# 2020-02-LPD3806-orig.net
KiCad netlist of a schematic drawn in EAGLE
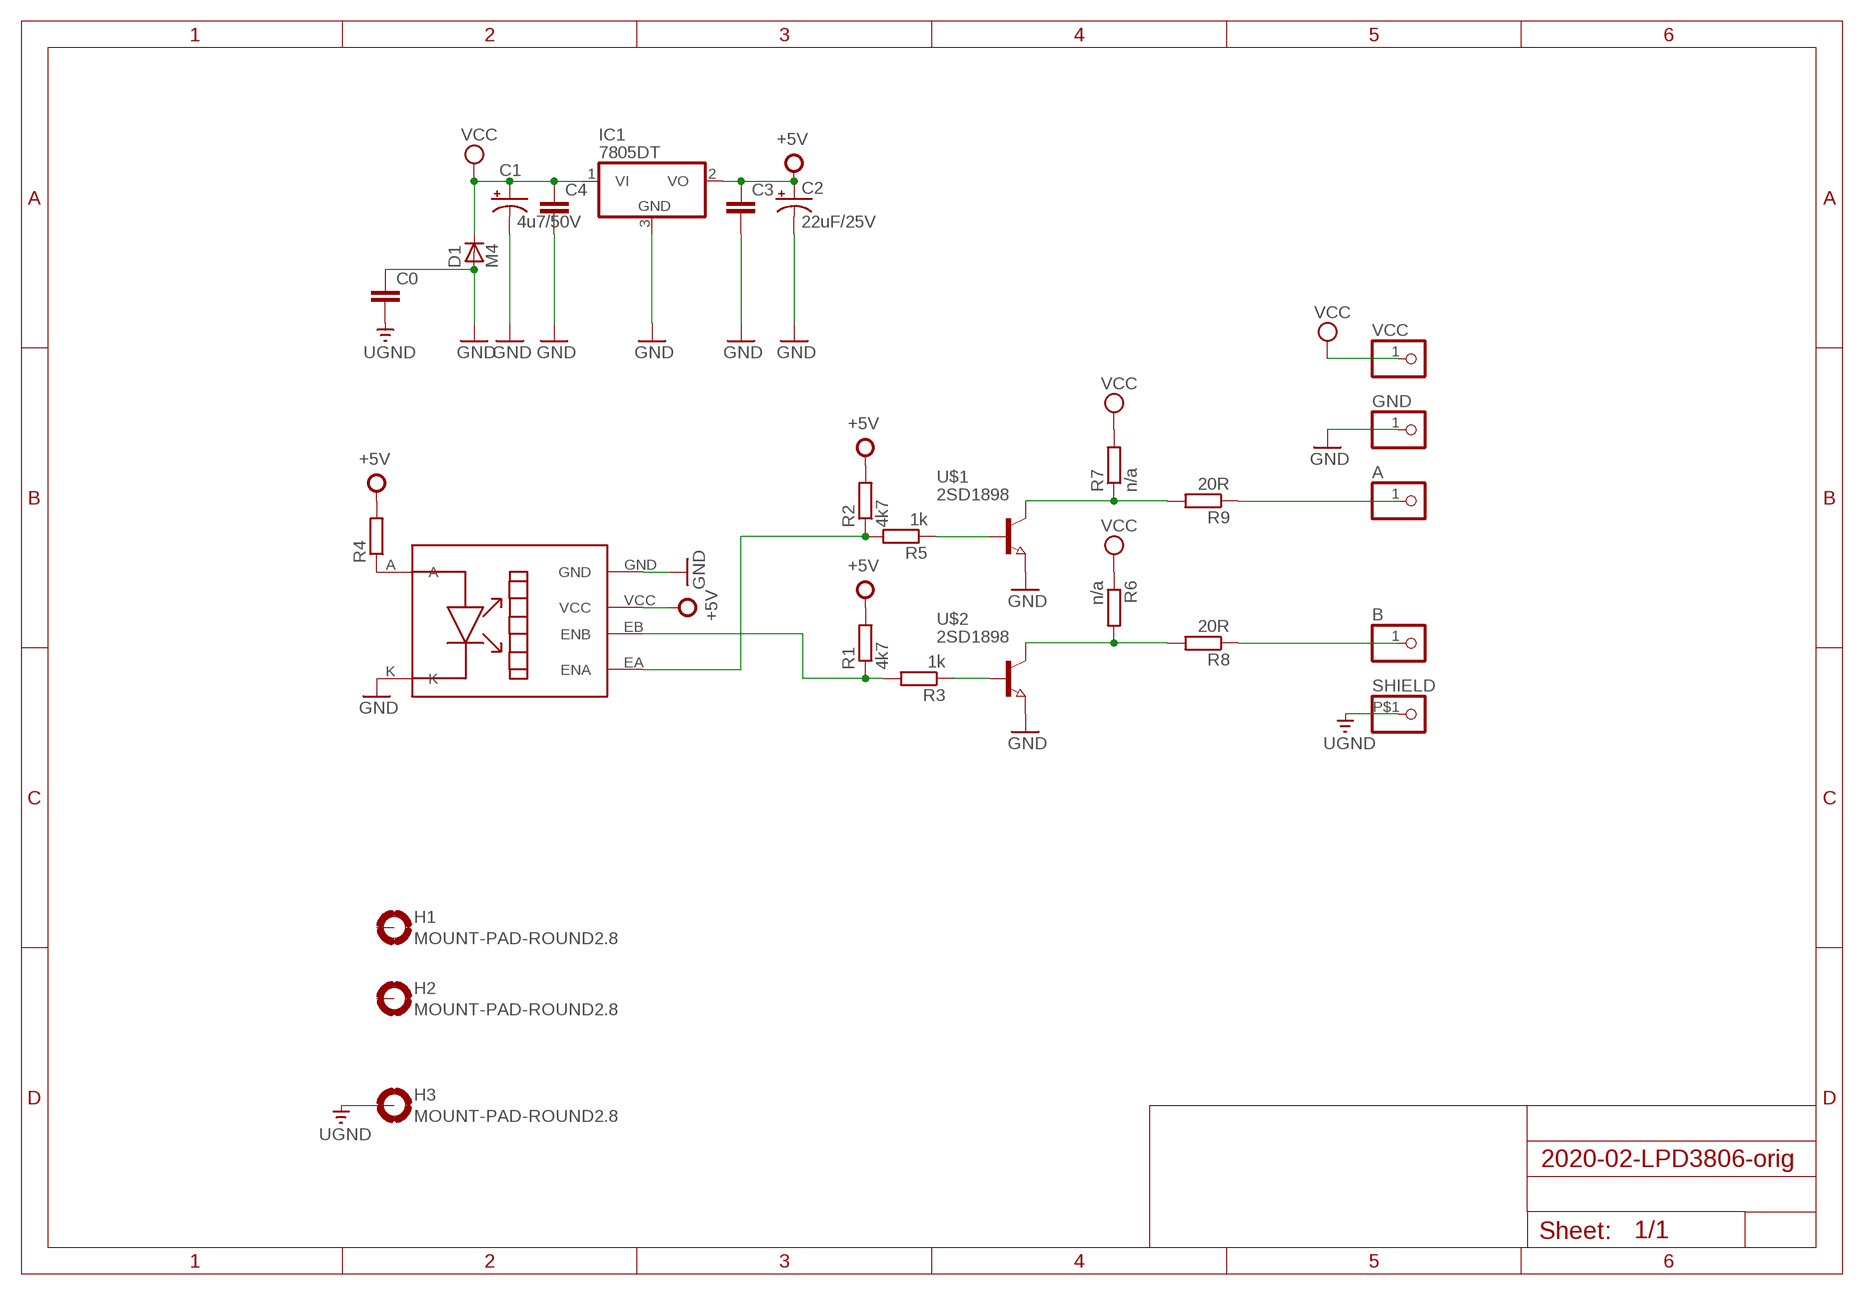
[diagram p0: schematic, sheet 1]

(export (version "E")
  (design (tool "Eeschema 10.0.6"))
  (components
    (comp (ref "A")
      (value "PINHD-1X1")
      (footprint "eagle-import:1X01")
      (libsource (lib "eagle-import") (part "PINHD-1X1"))
    )
    (comp (ref "B")
      (value "PINHD-1X1")
      (footprint "eagle-import:1X01")
      (libsource (lib "eagle-import") (part "PINHD-1X1"))
    )
    (comp (ref "C0")
      (value "C-EUC1206")
      (footprint "eagle-import:C1206")
      (libsource (lib "eagle-import") (part "C-EUC1206"))
    )
    (comp (ref "C1")
      (value "4u7/50V")
      (footprint "eagle-import:153CLV-0405")
      (libsource (lib "eagle-import") (part "CPOL-US153CLV-0405"))
    )
    (comp (ref "C2")
      (value "22uF/25V")
      (footprint "eagle-import:153CLV-0505")
      (libsource (lib "eagle-import") (part "CPOL-US153CLV-0505"))
    )
    (comp (ref "C3")
      (value "C-EUC0805")
      (footprint "eagle-import:C0805")
      (libsource (lib "eagle-import") (part "C-EUC0805"))
    )
    (comp (ref "C4")
      (value "C-EUC0805")
      (footprint "eagle-import:C0805")
      (libsource (lib "eagle-import") (part "C-EUC0805"))
    )
    (comp (ref "D1")
      (value "M4")
      (footprint "eagle-import:SOD-123")
      (libsource (lib "eagle-import") (part "DIODESOD-123"))
    )
    (comp (ref "GND")
      (value "PINHD-1X1")
      (footprint "eagle-import:1X01")
      (libsource (lib "eagle-import") (part "PINHD-1X1"))
    )
    (comp (ref "H1")
      (value "MOUNT-PAD-ROUND2.8")
      (footprint "eagle-import:2,8-PAD")
      (libsource (lib "eagle-import") (part "MOUNT-PAD-ROUND2.8"))
    )
    (comp (ref "H2")
      (value "MOUNT-PAD-ROUND2.8")
      (footprint "eagle-import:2,8-PAD")
      (libsource (lib "eagle-import") (part "MOUNT-PAD-ROUND2.8"))
    )
    (comp (ref "H3")
      (value "MOUNT-PAD-ROUND2.8")
      (footprint "eagle-import:2,8-PAD")
      (libsource (lib "eagle-import") (part "MOUNT-PAD-ROUND2.8"))
    )
    (comp (ref "IC1")
      (value "7805DT")
      (footprint "eagle-import:TO252")
      (libsource (lib "eagle-import") (part "78DT05"))
    )
    (comp (ref "R1")
      (value "4k7")
      (footprint "eagle-import:R0805")
      (libsource (lib "eagle-import") (part "R-EU_R0805"))
    )
    (comp (ref "R2")
      (value "4k7")
      (footprint "eagle-import:R0805")
      (libsource (lib "eagle-import") (part "R-EU_R0805"))
    )
    (comp (ref "R3")
      (value "1k")
      (footprint "eagle-import:R0805")
      (libsource (lib "eagle-import") (part "R-EU_R0805"))
    )
    (comp (ref "R4")
      (value "R-EU_R1206")
      (footprint "eagle-import:R1206")
      (libsource (lib "eagle-import") (part "R-EU_R1206"))
    )
    (comp (ref "R5")
      (value "1k")
      (footprint "eagle-import:R0805")
      (libsource (lib "eagle-import") (part "R-EU_R0805"))
    )
    (comp (ref "R6")
      (value "n/a")
      (footprint "eagle-import:R1206")
      (libsource (lib "eagle-import") (part "R-EU_R1206"))
    )
    (comp (ref "R7")
      (value "n/a")
      (footprint "eagle-import:R1206")
      (libsource (lib "eagle-import") (part "R-EU_R1206"))
    )
    (comp (ref "R8")
      (value "20R")
      (footprint "eagle-import:R1206")
      (libsource (lib "eagle-import") (part "R-EU_R1206"))
    )
    (comp (ref "R9")
      (value "20R")
      (footprint "eagle-import:R1206")
      (libsource (lib "eagle-import") (part "R-EU_R1206"))
    )
    (comp (ref "SHIELD")
      (value "PINHD-1X1-BIGPOGO")
      (footprint "eagle-import:1X1-BIGPOGO")
      (libsource (lib "eagle-import") (part "PINHD-1X1-BIGPOGO"))
    )
    (comp (ref "U$1")
      (value "2SD1898")
      (footprint "eagle-import:SOT-89")
      (libsource (lib "eagle-import") (part "2SD1898"))
    )
    (comp (ref "U$2")
      (value "2SD1898")
      (footprint "eagle-import:SOT-89")
      (libsource (lib "eagle-import") (part "2SD1898"))
    )
    (comp (ref "U$3")
      (value "N30-6841")
      (footprint "eagle-import:N30-6841")
      (libsource (lib "eagle-import") (part "N30-6841"))
    )
    (comp (ref "VCC")
      (value "PINHD-1X1")
      (footprint "eagle-import:1X01")
      (libsource (lib "eagle-import") (part "PINHD-1X1"))
    )
  )
  (nets
    (net (code "1") (name "+5V") (class "Default")
      (node (ref "C2") (pin "+") (pinfunction "+_+") (pintype "passive"))
      (node (ref "C3") (pin "1") (pinfunction "1_1") (pintype "passive"))
      (node (ref "IC1") (pin "2") (pinfunction "VO_2") (pintype "passive"))
      (node (ref "R1") (pin "2") (pinfunction "2_2") (pintype "passive"))
      (node (ref "R2") (pin "2") (pinfunction "2_2") (pintype "passive"))
      (node (ref "R4") (pin "2") (pinfunction "2_2") (pintype "passive"))
      (node (ref "U$3") (pin "VCC") (pinfunction "VCC_VCC") (pintype "power_in"))
    )
    (net (code "2") (name "GND") (class "Default")
      (node (ref "C0") (pin "1") (pinfunction "1_1") (pintype "passive"))
      (node (ref "C1") (pin "-") (pinfunction "-_-") (pintype "passive"))
      (node (ref "C2") (pin "-") (pinfunction "-_-") (pintype "passive"))
      (node (ref "C3") (pin "2") (pinfunction "2_2") (pintype "passive"))
      (node (ref "C4") (pin "2") (pinfunction "2_2") (pintype "passive"))
      (node (ref "D1") (pin "A") (pinfunction "A_A") (pintype "passive"))
      (node (ref "GND") (pin "1") (pinfunction "1_1") (pintype "passive"))
      (node (ref "IC1") (pin "3") (pinfunction "GND_3") (pintype "passive"))
      (node (ref "U$1") (pin "E") (pinfunction "E_E") (pintype "passive"))
      (node (ref "U$2") (pin "E") (pinfunction "E_E") (pintype "passive"))
      (node (ref "U$3") (pin "GND") (pinfunction "GND_GND") (pintype "power_in"))
      (node (ref "U$3") (pin "K") (pinfunction "K_K") (pintype "bidirectional"))
    )
    (net (code "3") (name "Net-(A-Pad1)") (class "Default")
      (node (ref "A") (pin "1") (pinfunction "1_1") (pintype "passive"))
      (node (ref "R9") (pin "1") (pinfunction "1_1") (pintype "passive"))
    )
    (net (code "4") (name "Net-(B-Pad1)") (class "Default")
      (node (ref "B") (pin "1") (pinfunction "1_1") (pintype "passive"))
      (node (ref "R8") (pin "1") (pinfunction "1_1") (pintype "passive"))
    )
    (net (code "5") (name "Net-(R3-Pad1)") (class "Default")
      (node (ref "R3") (pin "1") (pinfunction "1_1") (pintype "passive"))
      (node (ref "U$2") (pin "B") (pinfunction "B_B") (pintype "passive"))
    )
    (net (code "6") (name "Net-(R4-Pad1)") (class "Default")
      (node (ref "R4") (pin "1") (pinfunction "1_1") (pintype "passive"))
      (node (ref "U$3") (pin "A") (pinfunction "A_A") (pintype "bidirectional"))
    )
    (net (code "7") (name "Net-(R5-Pad1)") (class "Default")
      (node (ref "R5") (pin "1") (pinfunction "1_1") (pintype "passive"))
      (node (ref "U$1") (pin "B") (pinfunction "B_B") (pintype "passive"))
    )
    (net (code "8") (name "Net-(R6-Pad2)") (class "Default")
      (node (ref "R6") (pin "2") (pinfunction "2_2") (pintype "passive"))
      (node (ref "R8") (pin "2") (pinfunction "2_2") (pintype "passive"))
      (node (ref "U$2") (pin "C1") (pinfunction "C_C1") (pintype "passive"))
      (node (ref "U$2") (pin "C2") (pinfunction "C_C2") (pintype "passive"))
    )
    (net (code "9") (name "Net-(R7-Pad1)") (class "Default")
      (node (ref "R7") (pin "1") (pinfunction "1_1") (pintype "passive"))
      (node (ref "R9") (pin "2") (pinfunction "2_2") (pintype "passive"))
      (node (ref "U$1") (pin "C1") (pinfunction "C_C1") (pintype "passive"))
      (node (ref "U$1") (pin "C2") (pinfunction "C_C2") (pintype "passive"))
    )
    (net (code "10") (name "Net-(U$3-ENA)") (class "Default")
      (node (ref "R2") (pin "1") (pinfunction "1_1") (pintype "passive"))
      (node (ref "R5") (pin "2") (pinfunction "2_2") (pintype "passive"))
      (node (ref "U$3") (pin "EA") (pinfunction "ENA_EA") (pintype "bidirectional"))
    )
    (net (code "11") (name "Net-(U$3-ENB)") (class "Default")
      (node (ref "R1") (pin "1") (pinfunction "1_1") (pintype "passive"))
      (node (ref "R3") (pin "2") (pinfunction "2_2") (pintype "passive"))
      (node (ref "U$3") (pin "EB") (pinfunction "ENB_EB") (pintype "bidirectional"))
    )
    (net (code "12") (name "UGND") (class "Default")
      (node (ref "C0") (pin "2") (pinfunction "2_2") (pintype "passive"))
      (node (ref "H3") (pin "B2,8") (pinfunction "MOUNT_B2,8") (pintype "passive"))
      (node (ref "SHIELD") (pin "P$1") (pinfunction "1_P$1") (pintype "passive"))
    )
    (net (code "13") (name "VCC") (class "Default")
      (node (ref "C1") (pin "+") (pinfunction "+_+") (pintype "passive"))
      (node (ref "C4") (pin "1") (pinfunction "1_1") (pintype "passive"))
      (node (ref "D1") (pin "C") (pinfunction "C_C") (pintype "passive"))
      (node (ref "IC1") (pin "1") (pinfunction "VI_1") (pintype "input"))
      (node (ref "R6") (pin "1") (pinfunction "1_1") (pintype "passive"))
      (node (ref "R7") (pin "2") (pinfunction "2_2") (pintype "passive"))
      (node (ref "VCC") (pin "1") (pinfunction "1_1") (pintype "passive"))
    )
    (net (code "14") (name "unconnected-(H1-MOUNT-PadB2,8)") (class "Default")
      (node (ref "H1") (pin "B2,8") (pinfunction "MOUNT_B2,8") (pintype "passive"))
    )
    (net (code "15") (name "unconnected-(H2-MOUNT-PadB2,8)") (class "Default")
      (node (ref "H2") (pin "B2,8") (pinfunction "MOUNT_B2,8") (pintype "passive"))
    )
  )
)
